# ControlBoardUsb.net
KiCad netlist of a schematic drawn in EAGLE
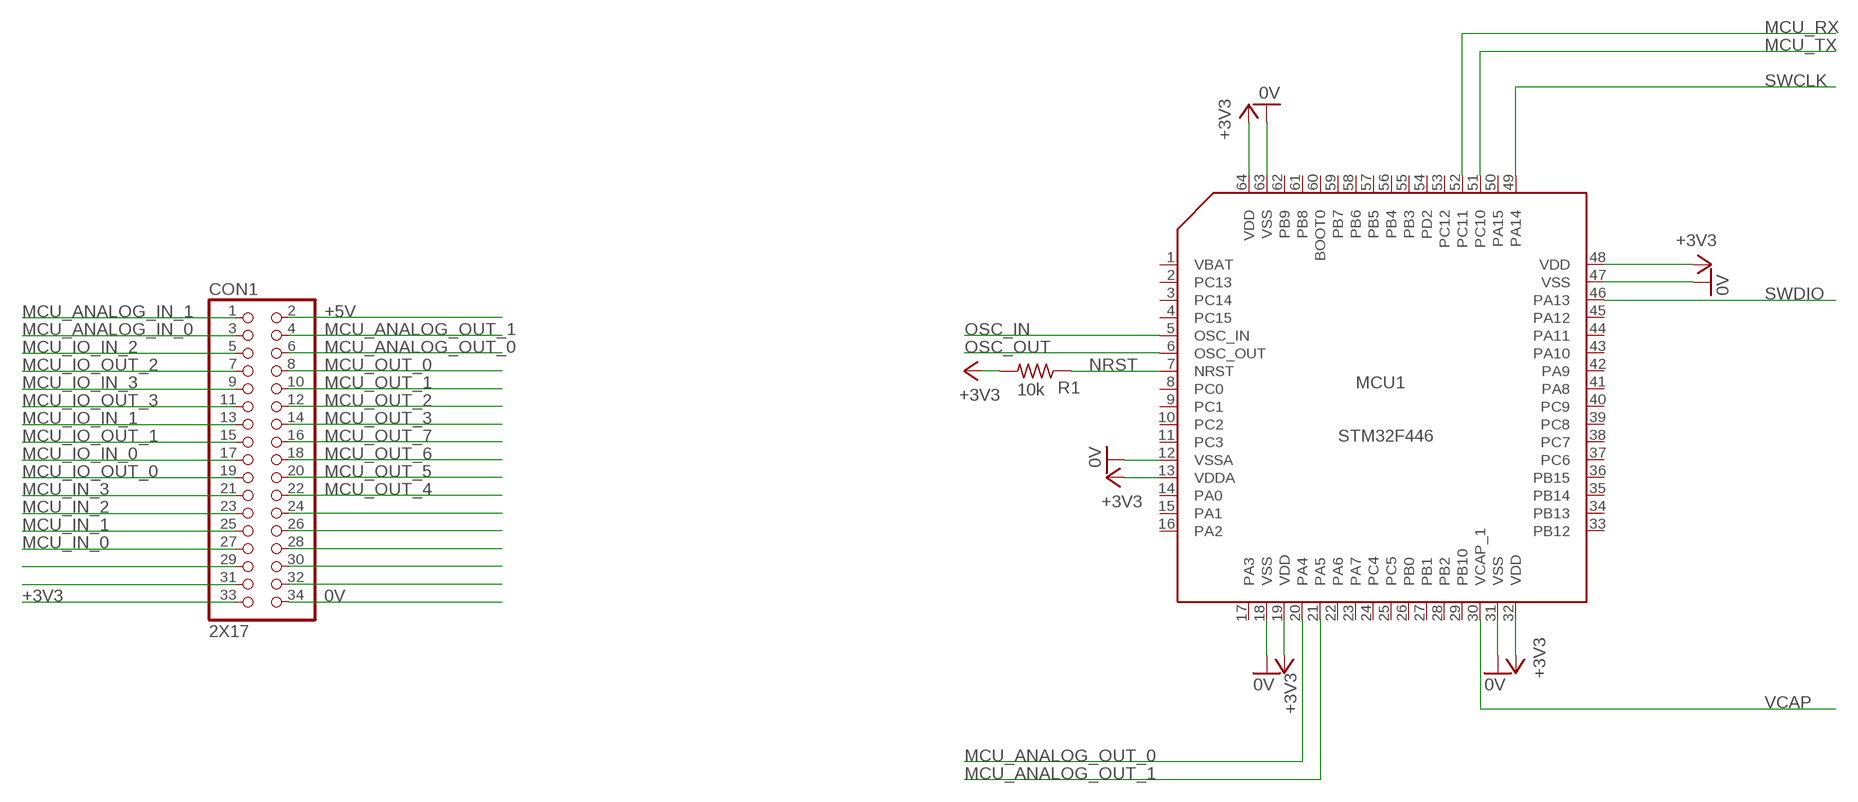
[diagram p0: schematic, sheet 1, part 1 of 2]
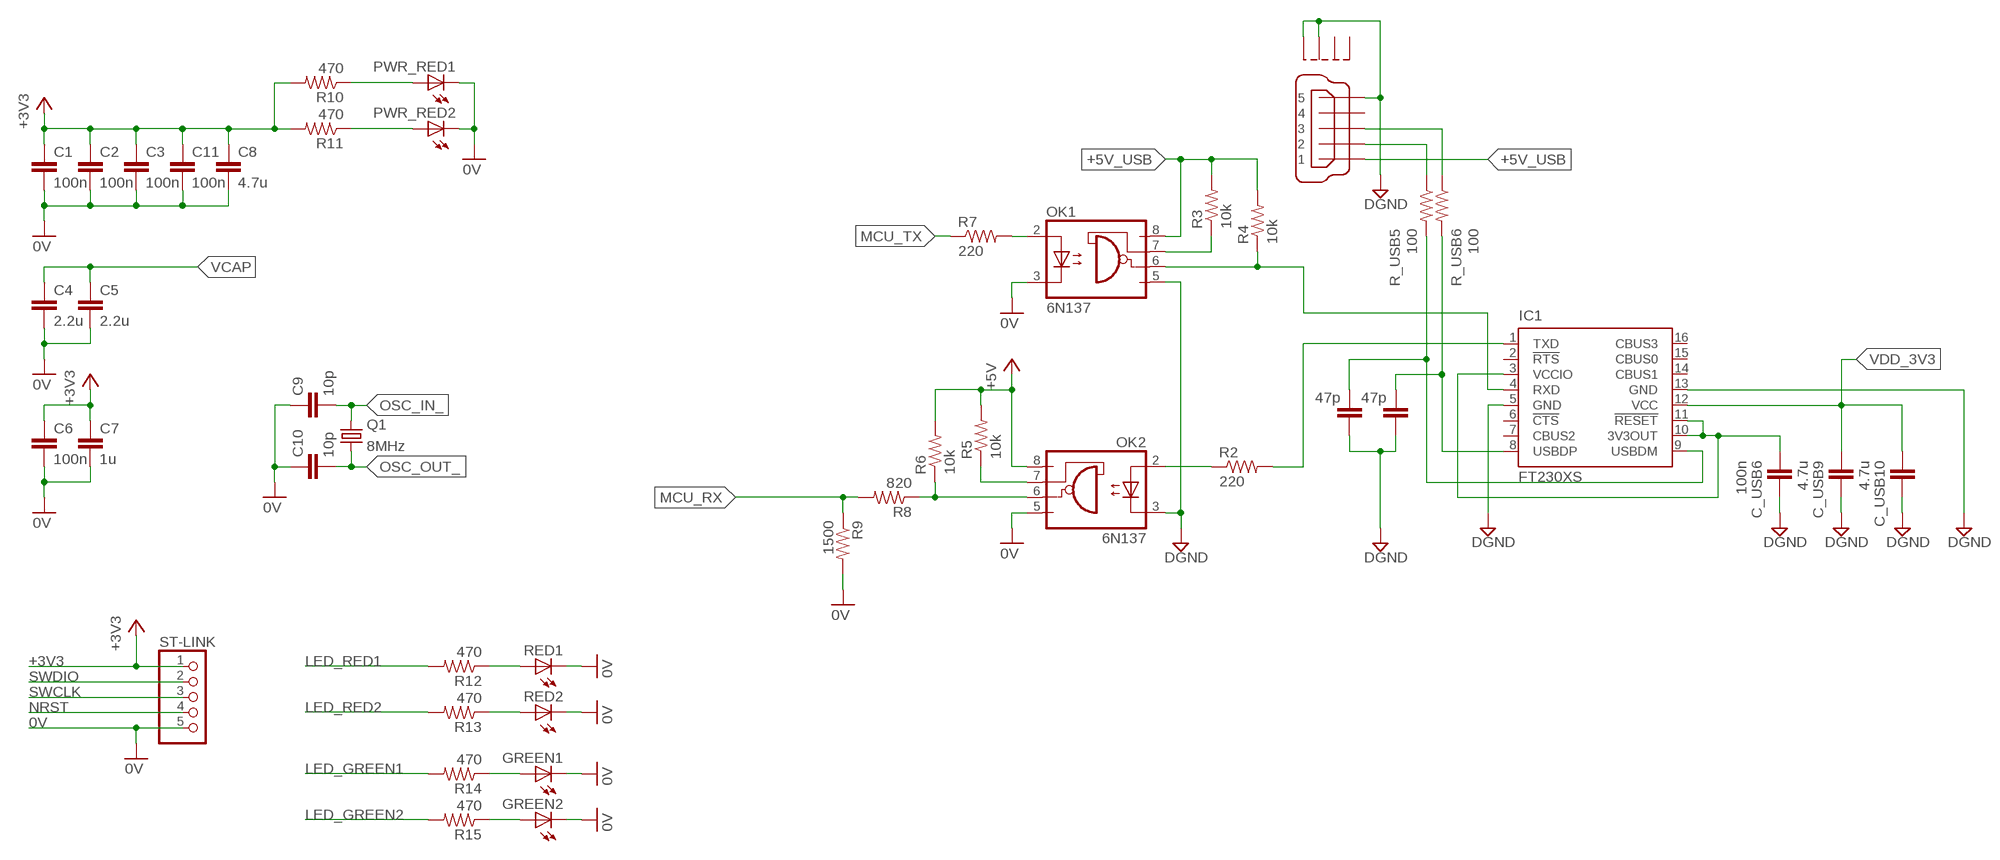
[diagram p1: schematic, sheet 1, part 2 of 2]

(export (version "E")
  (design (tool "Eeschema 10.0.6"))
  (components
    (comp (ref "C1")
      (value "100n")
      (footprint "eagle-import:C0402")
      (libsource (lib "eagle-import") (part "C-EUC0402"))
    )
    (comp (ref "C2")
      (value "100n")
      (footprint "eagle-import:C0402")
      (libsource (lib "eagle-import") (part "C-EUC0402"))
    )
    (comp (ref "C3")
      (value "100n")
      (footprint "eagle-import:C0402")
      (libsource (lib "eagle-import") (part "C-EUC0402"))
    )
    (comp (ref "C4")
      (value "2.2u")
      (footprint "eagle-import:C0402")
      (libsource (lib "eagle-import") (part "C-EUC0402"))
    )
    (comp (ref "C5")
      (value "2.2u")
      (footprint "eagle-import:C0402")
      (libsource (lib "eagle-import") (part "C-EUC0402"))
    )
    (comp (ref "C6")
      (value "100n")
      (footprint "eagle-import:C0402")
      (libsource (lib "eagle-import") (part "C-EUC0402"))
    )
    (comp (ref "C7")
      (value "1u")
      (footprint "eagle-import:C0402")
      (libsource (lib "eagle-import") (part "C-EUC0402"))
    )
    (comp (ref "C8")
      (value "4.7u")
      (footprint "eagle-import:C0402")
      (libsource (lib "eagle-import") (part "C-EUC0402"))
    )
    (comp (ref "C9")
      (value "10p")
      (footprint "eagle-import:C0402")
      (libsource (lib "eagle-import") (part "C-EUC0402"))
    )
    (comp (ref "C10")
      (value "10p")
      (footprint "eagle-import:C0402")
      (libsource (lib "eagle-import") (part "C-EUC0402"))
    )
    (comp (ref "C11")
      (value "100n")
      (footprint "eagle-import:C0402")
      (libsource (lib "eagle-import") (part "C-EUC0402"))
    )
    (comp (ref "CON1")
      (value "2X17")
      (footprint "eagle-import:2X17")
      (libsource (lib "eagle-import") (part "2X17"))
    )
    (comp (ref "CON3")
      (value "MICRO_USB_TYPE_A")
      (footprint "eagle-import:MINI_USB_TYPE_A_THOLE")
      (libsource (lib "eagle-import") (part "MICRO_USB_TYPE_A"))
    )
    (comp (ref "C_USB6")
      (value "100n")
      (footprint "eagle-import:C0402")
      (libsource (lib "eagle-import") (part "C-EUC0402"))
    )
    (comp (ref "C_USB7")
      (value "47p")
      (footprint "eagle-import:C0402")
      (libsource (lib "eagle-import") (part "C-EUC0402"))
    )
    (comp (ref "C_USB8")
      (value "47p")
      (footprint "eagle-import:C0402")
      (libsource (lib "eagle-import") (part "C-EUC0402"))
    )
    (comp (ref "C_USB9")
      (value "4.7u")
      (footprint "eagle-import:C0402")
      (libsource (lib "eagle-import") (part "C-EUC0402"))
    )
    (comp (ref "C_USB10")
      (value "4.7u")
      (footprint "eagle-import:C0402")
      (libsource (lib "eagle-import") (part "C-EUC0402"))
    )
    (comp (ref "GREEN1")
      (value "LEDCHIP-LED0805")
      (footprint "eagle-import:CHIP-LED0805")
      (libsource (lib "eagle-import") (part "LEDCHIP-LED0805"))
    )
    (comp (ref "GREEN2")
      (value "LEDCHIP-LED0805")
      (footprint "eagle-import:CHIP-LED0805")
      (libsource (lib "eagle-import") (part "LEDCHIP-LED0805"))
    )
    (comp (ref "IC1")
      (value "FT230XS")
      (footprint "eagle-import:SSOP16")
      (libsource (lib "eagle-import") (part "FT230XS"))
    )
    (comp (ref "MCU1")
      (value "STM32F446")
      (footprint "eagle-import:LQFP-64")
      (libsource (lib "eagle-import") (part "STM32F446"))
    )
    (comp (ref "OK1")
      (value "6N137")
      (footprint "eagle-import:DIL08")
      (libsource (lib "eagle-import") (part "6N137"))
    )
    (comp (ref "OK2")
      (value "6N137")
      (footprint "eagle-import:DIL08")
      (libsource (lib "eagle-import") (part "6N137"))
    )
    (comp (ref "PWR_RED1")
      (value "LEDCHIP-LED0805")
      (footprint "eagle-import:CHIP-LED0805")
      (libsource (lib "eagle-import") (part "LEDCHIP-LED0805"))
    )
    (comp (ref "PWR_RED2")
      (value "LEDCHIP-LED0805")
      (footprint "eagle-import:CHIP-LED0805")
      (libsource (lib "eagle-import") (part "LEDCHIP-LED0805"))
    )
    (comp (ref "Q1")
      (value "8MHz")
      (footprint "eagle-import:HC33U-V")
      (libsource (lib "eagle-import") (part "CRYSTALHC33U-V"))
    )
    (comp (ref "R1")
      (value "10k")
      (footprint "eagle-import:R0402")
      (libsource (lib "eagle-import") (part "R-US_R0402"))
    )
    (comp (ref "R2")
      (value "220")
      (footprint "eagle-import:R0402")
      (libsource (lib "eagle-import") (part "R-US_R0402"))
    )
    (comp (ref "R3")
      (value "10k")
      (footprint "eagle-import:R0402")
      (libsource (lib "eagle-import") (part "R-US_R0402"))
    )
    (comp (ref "R4")
      (value "10k")
      (footprint "eagle-import:R0402")
      (libsource (lib "eagle-import") (part "R-US_R0402"))
    )
    (comp (ref "R5")
      (value "10k")
      (footprint "eagle-import:R0402")
      (libsource (lib "eagle-import") (part "R-US_R0402"))
    )
    (comp (ref "R6")
      (value "10k")
      (footprint "eagle-import:R0402")
      (libsource (lib "eagle-import") (part "R-US_R0402"))
    )
    (comp (ref "R7")
      (value "220")
      (footprint "eagle-import:R0402")
      (libsource (lib "eagle-import") (part "R-US_R0402"))
    )
    (comp (ref "R8")
      (value "820")
      (footprint "eagle-import:R0402")
      (libsource (lib "eagle-import") (part "R-US_R0402"))
    )
    (comp (ref "R9")
      (value "1500")
      (footprint "eagle-import:R0402")
      (libsource (lib "eagle-import") (part "R-US_R0402"))
    )
    (comp (ref "R10")
      (value "470")
      (footprint "eagle-import:R0402")
      (libsource (lib "eagle-import") (part "R-US_R0402"))
    )
    (comp (ref "R11")
      (value "470")
      (footprint "eagle-import:R0402")
      (libsource (lib "eagle-import") (part "R-US_R0402"))
    )
    (comp (ref "R12")
      (value "470")
      (footprint "eagle-import:R0402")
      (libsource (lib "eagle-import") (part "R-US_R0402"))
    )
    (comp (ref "R13")
      (value "470")
      (footprint "eagle-import:R0402")
      (libsource (lib "eagle-import") (part "R-US_R0402"))
    )
    (comp (ref "R14")
      (value "470")
      (footprint "eagle-import:R0402")
      (libsource (lib "eagle-import") (part "R-US_R0402"))
    )
    (comp (ref "R15")
      (value "470")
      (footprint "eagle-import:R0402")
      (libsource (lib "eagle-import") (part "R-US_R0402"))
    )
    (comp (ref "RED1")
      (value "LEDCHIP-LED0805")
      (footprint "eagle-import:CHIP-LED0805")
      (libsource (lib "eagle-import") (part "LEDCHIP-LED0805"))
    )
    (comp (ref "RED2")
      (value "LEDCHIP-LED0805")
      (footprint "eagle-import:CHIP-LED0805")
      (libsource (lib "eagle-import") (part "LEDCHIP-LED0805"))
    )
    (comp (ref "R_USB5")
      (value "100")
      (footprint "eagle-import:R0402")
      (libsource (lib "eagle-import") (part "R-US_R0402"))
    )
    (comp (ref "R_USB6")
      (value "100")
      (footprint "eagle-import:R0402")
      (libsource (lib "eagle-import") (part "R-US_R0402"))
    )
    (comp (ref "ST-LINK")
      (value "PINHD-1X5/90")
      (footprint "eagle-import:1X05_90")
      (libsource (lib "eagle-import") (part "PINHD-1X5/90"))
    )
  )
  (nets
    (net (code "1") (name "+3V3") (class "Default")
      (node (ref "C1") (pin "1") (pinfunction "1_1") (pintype "passive"))
      (node (ref "C11") (pin "1") (pinfunction "1_1") (pintype "passive"))
      (node (ref "C2") (pin "1") (pinfunction "1_1") (pintype "passive"))
      (node (ref "C3") (pin "1") (pinfunction "1_1") (pintype "passive"))
      (node (ref "C6") (pin "1") (pinfunction "1_1") (pintype "passive"))
      (node (ref "C7") (pin "1") (pinfunction "1_1") (pintype "passive"))
      (node (ref "C8") (pin "1") (pinfunction "1_1") (pintype "passive"))
      (node (ref "CON1") (pin "33") (pinfunction "33_33") (pintype "passive"))
      (node (ref "MCU1") (pin "13") (pinfunction "VDDA_13") (pintype "bidirectional"))
      (node (ref "MCU1") (pin "19") (pinfunction "VDD_19") (pintype "bidirectional"))
      (node (ref "MCU1") (pin "32") (pinfunction "VDD_32") (pintype "bidirectional"))
      (node (ref "MCU1") (pin "48") (pinfunction "VDD_48") (pintype "bidirectional"))
      (node (ref "MCU1") (pin "64") (pinfunction "VDD_64") (pintype "bidirectional"))
      (node (ref "R1") (pin "2") (pinfunction "2_2") (pintype "passive"))
      (node (ref "R10") (pin "2") (pinfunction "2_2") (pintype "passive"))
      (node (ref "R11") (pin "2") (pinfunction "2_2") (pintype "passive"))
      (node (ref "ST-LINK") (pin "1") (pinfunction "1_1") (pintype "passive"))
    )
    (net (code "2") (name "+5V") (class "Default")
      (node (ref "CON1") (pin "2") (pinfunction "2_2") (pintype "passive"))
      (node (ref "OK2") (pin "8") (pinfunction "VCC_8") (pintype "passive"))
      (node (ref "R5") (pin "2") (pinfunction "2_2") (pintype "passive"))
      (node (ref "R6") (pin "2") (pinfunction "2_2") (pintype "passive"))
    )
    (net (code "3") (name "+5V_USB") (class "Default")
      (node (ref "CON3") (pin "1") (pinfunction "1_1") (pintype "passive"))
      (node (ref "OK1") (pin "8") (pinfunction "VCC_8") (pintype "passive"))
      (node (ref "R3") (pin "2") (pinfunction "2_2") (pintype "passive"))
      (node (ref "R4") (pin "2") (pinfunction "2_2") (pintype "passive"))
    )
    (net (code "4") (name "/LED_GREEN1") (class "Default")
      (node (ref "R14") (pin "2") (pinfunction "2_2") (pintype "passive"))
    )
    (net (code "5") (name "/LED_GREEN2") (class "Default")
      (node (ref "R15") (pin "2") (pinfunction "2_2") (pintype "passive"))
    )
    (net (code "6") (name "/LED_RED1") (class "Default")
      (node (ref "R12") (pin "2") (pinfunction "2_2") (pintype "passive"))
    )
    (net (code "7") (name "/LED_RED2") (class "Default")
      (node (ref "R13") (pin "2") (pinfunction "2_2") (pintype "passive"))
    )
    (net (code "8") (name "/MCU_ANALOG_IN_0") (class "Default")
      (node (ref "CON1") (pin "3") (pinfunction "3_3") (pintype "passive"))
    )
    (net (code "9") (name "/MCU_ANALOG_IN_1") (class "Default")
      (node (ref "CON1") (pin "1") (pinfunction "1_1") (pintype "passive"))
    )
    (net (code "10") (name "/MCU_ANALOG_OUT_0") (class "Default")
      (node (ref "CON1") (pin "6") (pinfunction "6_6") (pintype "passive"))
      (node (ref "MCU1") (pin "20") (pinfunction "PA4_20") (pintype "bidirectional"))
    )
    (net (code "11") (name "/MCU_ANALOG_OUT_1") (class "Default")
      (node (ref "CON1") (pin "4") (pinfunction "4_4") (pintype "passive"))
      (node (ref "MCU1") (pin "21") (pinfunction "PA5_21") (pintype "bidirectional"))
    )
    (net (code "12") (name "/MCU_IN_0") (class "Default")
      (node (ref "CON1") (pin "27") (pinfunction "27_27") (pintype "passive"))
    )
    (net (code "13") (name "/MCU_IN_1") (class "Default")
      (node (ref "CON1") (pin "25") (pinfunction "25_25") (pintype "passive"))
    )
    (net (code "14") (name "/MCU_IN_2") (class "Default")
      (node (ref "CON1") (pin "23") (pinfunction "23_23") (pintype "passive"))
    )
    (net (code "15") (name "/MCU_IN_3") (class "Default")
      (node (ref "CON1") (pin "21") (pinfunction "21_21") (pintype "passive"))
    )
    (net (code "16") (name "/MCU_IO_IN_0") (class "Default")
      (node (ref "CON1") (pin "17") (pinfunction "17_17") (pintype "passive"))
    )
    (net (code "17") (name "/MCU_IO_IN_1") (class "Default")
      (node (ref "CON1") (pin "13") (pinfunction "13_13") (pintype "passive"))
    )
    (net (code "18") (name "/MCU_IO_IN_2") (class "Default")
      (node (ref "CON1") (pin "5") (pinfunction "5_5") (pintype "passive"))
    )
    (net (code "19") (name "/MCU_IO_IN_3") (class "Default")
      (node (ref "CON1") (pin "9") (pinfunction "9_9") (pintype "passive"))
    )
    (net (code "20") (name "/MCU_IO_OUT_0") (class "Default")
      (node (ref "CON1") (pin "19") (pinfunction "19_19") (pintype "passive"))
    )
    (net (code "21") (name "/MCU_IO_OUT_1") (class "Default")
      (node (ref "CON1") (pin "15") (pinfunction "15_15") (pintype "passive"))
    )
    (net (code "22") (name "/MCU_IO_OUT_2") (class "Default")
      (node (ref "CON1") (pin "7") (pinfunction "7_7") (pintype "passive"))
    )
    (net (code "23") (name "/MCU_IO_OUT_3") (class "Default")
      (node (ref "CON1") (pin "11") (pinfunction "11_11") (pintype "passive"))
    )
    (net (code "24") (name "/MCU_OUT_0") (class "Default")
      (node (ref "CON1") (pin "8") (pinfunction "8_8") (pintype "passive"))
    )
    (net (code "25") (name "/MCU_OUT_1") (class "Default")
      (node (ref "CON1") (pin "10") (pinfunction "10_10") (pintype "passive"))
    )
    (net (code "26") (name "/MCU_OUT_2") (class "Default")
      (node (ref "CON1") (pin "12") (pinfunction "12_12") (pintype "passive"))
    )
    (net (code "27") (name "/MCU_OUT_3") (class "Default")
      (node (ref "CON1") (pin "14") (pinfunction "14_14") (pintype "passive"))
    )
    (net (code "28") (name "/MCU_OUT_4") (class "Default")
      (node (ref "CON1") (pin "22") (pinfunction "22_22") (pintype "passive"))
    )
    (net (code "29") (name "/MCU_OUT_5") (class "Default")
      (node (ref "CON1") (pin "20") (pinfunction "20_20") (pintype "passive"))
    )
    (net (code "30") (name "/MCU_OUT_6") (class "Default")
      (node (ref "CON1") (pin "18") (pinfunction "18_18") (pintype "passive"))
    )
    (net (code "31") (name "/MCU_OUT_7") (class "Default")
      (node (ref "CON1") (pin "16") (pinfunction "16_16") (pintype "passive"))
    )
    (net (code "32") (name "/NRST") (class "Default")
      (node (ref "MCU1") (pin "7") (pinfunction "NRST_7") (pintype "bidirectional"))
      (node (ref "R1") (pin "1") (pinfunction "1_1") (pintype "passive"))
      (node (ref "ST-LINK") (pin "4") (pinfunction "4_4") (pintype "passive"))
    )
    (net (code "33") (name "/OSC_IN") (class "Default")
      (node (ref "MCU1") (pin "5") (pinfunction "OSC_IN_5") (pintype "bidirectional"))
    )
    (net (code "34") (name "/OSC_OUT") (class "Default")
      (node (ref "MCU1") (pin "6") (pinfunction "OSC_OUT_6") (pintype "bidirectional"))
    )
    (net (code "35") (name "/SWCLK") (class "Default")
      (node (ref "MCU1") (pin "49") (pinfunction "PA14_49") (pintype "bidirectional"))
      (node (ref "ST-LINK") (pin "3") (pinfunction "3_3") (pintype "passive"))
    )
    (net (code "36") (name "/SWDIO") (class "Default")
      (node (ref "MCU1") (pin "46") (pinfunction "PA13_46") (pintype "bidirectional"))
      (node (ref "ST-LINK") (pin "2") (pinfunction "2_2") (pintype "passive"))
    )
    (net (code "37") (name "0V") (class "Default")
      (node (ref "C1") (pin "2") (pinfunction "2_2") (pintype "passive"))
      (node (ref "C10") (pin "1") (pinfunction "1_1") (pintype "passive"))
      (node (ref "C11") (pin "2") (pinfunction "2_2") (pintype "passive"))
      (node (ref "C2") (pin "2") (pinfunction "2_2") (pintype "passive"))
      (node (ref "C3") (pin "2") (pinfunction "2_2") (pintype "passive"))
      (node (ref "C4") (pin "2") (pinfunction "2_2") (pintype "passive"))
      (node (ref "C5") (pin "2") (pinfunction "2_2") (pintype "passive"))
      (node (ref "C6") (pin "2") (pinfunction "2_2") (pintype "passive"))
      (node (ref "C7") (pin "2") (pinfunction "2_2") (pintype "passive"))
      (node (ref "C8") (pin "2") (pinfunction "2_2") (pintype "passive"))
      (node (ref "C9") (pin "1") (pinfunction "1_1") (pintype "passive"))
      (node (ref "CON1") (pin "34") (pinfunction "34_34") (pintype "passive"))
      (node (ref "GREEN1") (pin "C") (pinfunction "C_C") (pintype "passive"))
      (node (ref "GREEN2") (pin "C") (pinfunction "C_C") (pintype "passive"))
      (node (ref "MCU1") (pin "12") (pinfunction "VSSA_12") (pintype "bidirectional"))
      (node (ref "MCU1") (pin "18") (pinfunction "VSS_18") (pintype "bidirectional"))
      (node (ref "MCU1") (pin "31") (pinfunction "VSS_31") (pintype "bidirectional"))
      (node (ref "MCU1") (pin "47") (pinfunction "VSS_47") (pintype "bidirectional"))
      (node (ref "MCU1") (pin "63") (pinfunction "VSS_63") (pintype "bidirectional"))
      (node (ref "OK1") (pin "3") (pinfunction "C_3") (pintype "passive"))
      (node (ref "OK2") (pin "5") (pinfunction "GND_5") (pintype "passive"))
      (node (ref "PWR_RED1") (pin "C") (pinfunction "C_C") (pintype "passive"))
      (node (ref "PWR_RED2") (pin "C") (pinfunction "C_C") (pintype "passive"))
      (node (ref "R9") (pin "2") (pinfunction "2_2") (pintype "passive"))
      (node (ref "RED1") (pin "C") (pinfunction "C_C") (pintype "passive"))
      (node (ref "RED2") (pin "C") (pinfunction "C_C") (pintype "passive"))
      (node (ref "ST-LINK") (pin "5") (pinfunction "5_5") (pintype "passive"))
    )
    (net (code "38") (name "DGND") (class "Default")
      (node (ref "CON3") (pin "5") (pinfunction "5_5") (pintype "passive"))
      (node (ref "CON3") (pin "M3") (pinfunction "S3_M3") (pintype "passive"))
      (node (ref "CON3") (pin "M4") (pinfunction "S4_M4") (pintype "passive"))
      (node (ref "C_USB10") (pin "1") (pinfunction "1_1") (pintype "passive"))
      (node (ref "C_USB6") (pin "1") (pinfunction "1_1") (pintype "passive"))
      (node (ref "C_USB7") (pin "1") (pinfunction "1_1") (pintype "passive"))
      (node (ref "C_USB8") (pin "1") (pinfunction "1_1") (pintype "passive"))
      (node (ref "C_USB9") (pin "1") (pinfunction "1_1") (pintype "passive"))
      (node (ref "IC1") (pin "13") (pinfunction "GND_13") (pintype "power_in"))
      (node (ref "IC1") (pin "5") (pinfunction "GND_5") (pintype "power_in"))
      (node (ref "OK1") (pin "5") (pinfunction "GND_5") (pintype "passive"))
      (node (ref "OK2") (pin "3") (pinfunction "C_3") (pintype "passive"))
    )
    (net (code "39") (name "MCU_RX") (class "Default")
      (node (ref "MCU1") (pin "52") (pinfunction "PC11_52") (pintype "bidirectional"))
      (node (ref "R8") (pin "2") (pinfunction "2_2") (pintype "passive"))
      (node (ref "R9") (pin "1") (pinfunction "1_1") (pintype "passive"))
    )
    (net (code "40") (name "MCU_TX") (class "Default")
      (node (ref "MCU1") (pin "51") (pinfunction "PC10_51") (pintype "bidirectional"))
      (node (ref "R7") (pin "1") (pinfunction "1_1") (pintype "passive"))
    )
    (net (code "41") (name "Net-(CON3-Pad2)") (class "Default")
      (node (ref "CON3") (pin "2") (pinfunction "2_2") (pintype "passive"))
      (node (ref "R_USB5") (pin "1") (pinfunction "1_1") (pintype "passive"))
    )
    (net (code "42") (name "Net-(CON3-Pad3)") (class "Default")
      (node (ref "CON3") (pin "3") (pinfunction "3_3") (pintype "passive"))
      (node (ref "R_USB6") (pin "1") (pinfunction "1_1") (pintype "passive"))
    )
    (net (code "43") (name "Net-(GREEN1-PadA)") (class "Default")
      (node (ref "GREEN1") (pin "A") (pinfunction "A_A") (pintype "passive"))
      (node (ref "R14") (pin "1") (pinfunction "1_1") (pintype "passive"))
    )
    (net (code "44") (name "Net-(GREEN2-PadA)") (class "Default")
      (node (ref "GREEN2") (pin "A") (pinfunction "A_A") (pintype "passive"))
      (node (ref "R15") (pin "1") (pinfunction "1_1") (pintype "passive"))
    )
    (net (code "45") (name "Net-(IC1-3V3OUT)") (class "Default")
      (node (ref "C_USB6") (pin "2") (pinfunction "2_2") (pintype "passive"))
      (node (ref "IC1") (pin "10") (pinfunction "3V3OUT_10") (pintype "output"))
      (node (ref "IC1") (pin "11") (pinfunction "~{RESET}_11") (pintype "input"))
      (node (ref "IC1") (pin "3") (pinfunction "VCCIO_3") (pintype "power_in"))
    )
    (net (code "46") (name "Net-(IC1-RXD)") (class "Default")
      (node (ref "IC1") (pin "4") (pinfunction "RXD_4") (pintype "input"))
      (node (ref "OK1") (pin "6") (pinfunction "VO_6") (pintype "passive"))
      (node (ref "R4") (pin "1") (pinfunction "1_1") (pintype "passive"))
    )
    (net (code "47") (name "Net-(IC1-TXD)") (class "Default")
      (node (ref "IC1") (pin "1") (pinfunction "TXD_1") (pintype "output"))
      (node (ref "R2") (pin "2") (pinfunction "2_2") (pintype "passive"))
    )
    (net (code "48") (name "Net-(IC1-USBDM)") (class "Default")
      (node (ref "C_USB7") (pin "2") (pinfunction "2_2") (pintype "passive"))
      (node (ref "IC1") (pin "9") (pinfunction "USBDM_9") (pintype "input"))
      (node (ref "R_USB5") (pin "2") (pinfunction "2_2") (pintype "passive"))
    )
    (net (code "49") (name "Net-(IC1-USBDP)") (class "Default")
      (node (ref "C_USB8") (pin "2") (pinfunction "2_2") (pintype "passive"))
      (node (ref "IC1") (pin "8") (pinfunction "USBDP_8") (pintype "input"))
      (node (ref "R_USB6") (pin "2") (pinfunction "2_2") (pintype "passive"))
    )
    (net (code "50") (name "Net-(OK1-A)") (class "Default")
      (node (ref "OK1") (pin "2") (pinfunction "A_2") (pintype "passive"))
      (node (ref "R7") (pin "2") (pinfunction "2_2") (pintype "passive"))
    )
    (net (code "51") (name "Net-(OK1-VE)") (class "Default")
      (node (ref "OK1") (pin "7") (pinfunction "VE_7") (pintype "passive"))
      (node (ref "R3") (pin "1") (pinfunction "1_1") (pintype "passive"))
    )
    (net (code "52") (name "Net-(OK2-A)") (class "Default")
      (node (ref "OK2") (pin "2") (pinfunction "A_2") (pintype "passive"))
      (node (ref "R2") (pin "1") (pinfunction "1_1") (pintype "passive"))
    )
    (net (code "53") (name "Net-(OK2-VE)") (class "Default")
      (node (ref "OK2") (pin "7") (pinfunction "VE_7") (pintype "passive"))
      (node (ref "R5") (pin "1") (pinfunction "1_1") (pintype "passive"))
    )
    (net (code "54") (name "Net-(OK2-VO)") (class "Default")
      (node (ref "OK2") (pin "6") (pinfunction "VO_6") (pintype "passive"))
      (node (ref "R6") (pin "1") (pinfunction "1_1") (pintype "passive"))
      (node (ref "R8") (pin "1") (pinfunction "1_1") (pintype "passive"))
    )
    (net (code "55") (name "Net-(PWR_RED1-PadA)") (class "Default")
      (node (ref "PWR_RED1") (pin "A") (pinfunction "A_A") (pintype "passive"))
      (node (ref "R10") (pin "1") (pinfunction "1_1") (pintype "passive"))
    )
    (net (code "56") (name "Net-(PWR_RED2-PadA)") (class "Default")
      (node (ref "PWR_RED2") (pin "A") (pinfunction "A_A") (pintype "passive"))
      (node (ref "R11") (pin "1") (pinfunction "1_1") (pintype "passive"))
    )
    (net (code "57") (name "Net-(R12-Pad1)") (class "Default")
      (node (ref "R12") (pin "1") (pinfunction "1_1") (pintype "passive"))
      (node (ref "RED1") (pin "A") (pinfunction "A_A") (pintype "passive"))
    )
    (net (code "58") (name "Net-(R13-Pad1)") (class "Default")
      (node (ref "R13") (pin "1") (pinfunction "1_1") (pintype "passive"))
      (node (ref "RED2") (pin "A") (pinfunction "A_A") (pintype "passive"))
    )
    (net (code "59") (name "OSC_IN_") (class "Default")
      (node (ref "C9") (pin "2") (pinfunction "2_2") (pintype "passive"))
      (node (ref "Q1") (pin "2") (pinfunction "2_2") (pintype "passive"))
    )
    (net (code "60") (name "OSC_OUT_") (class "Default")
      (node (ref "C10") (pin "2") (pinfunction "2_2") (pintype "passive"))
      (node (ref "Q1") (pin "1") (pinfunction "1_1") (pintype "passive"))
    )
    (net (code "61") (name "VCAP") (class "Default")
      (node (ref "C4") (pin "1") (pinfunction "1_1") (pintype "passive"))
      (node (ref "C5") (pin "1") (pinfunction "1_1") (pintype "passive"))
      (node (ref "MCU1") (pin "30") (pinfunction "VCAP_1_30") (pintype "bidirectional"))
    )
    (net (code "62") (name "VDD_3V3") (class "Default")
      (node (ref "C_USB10") (pin "2") (pinfunction "2_2") (pintype "passive"))
      (node (ref "C_USB9") (pin "2") (pinfunction "2_2") (pintype "passive"))
      (node (ref "IC1") (pin "12") (pinfunction "VCC_12") (pintype "power_in"))
    )
    (net (code "63") (name "unconnected-(CON1-Pad24)") (class "Default")
      (node (ref "CON1") (pin "24") (pinfunction "24_24") (pintype "passive"))
    )
    (net (code "64") (name "unconnected-(CON1-Pad26)") (class "Default")
      (node (ref "CON1") (pin "26") (pinfunction "26_26") (pintype "passive"))
    )
    (net (code "65") (name "unconnected-(CON1-Pad28)") (class "Default")
      (node (ref "CON1") (pin "28") (pinfunction "28_28") (pintype "passive"))
    )
    (net (code "66") (name "unconnected-(CON1-Pad29)") (class "Default")
      (node (ref "CON1") (pin "29") (pinfunction "29_29") (pintype "passive"))
    )
    (net (code "67") (name "unconnected-(CON1-Pad30)") (class "Default")
      (node (ref "CON1") (pin "30") (pinfunction "30_30") (pintype "passive"))
    )
    (net (code "68") (name "unconnected-(CON1-Pad31)") (class "Default")
      (node (ref "CON1") (pin "31") (pinfunction "31_31") (pintype "passive"))
    )
    (net (code "69") (name "unconnected-(CON1-Pad32)") (class "Default")
      (node (ref "CON1") (pin "32") (pinfunction "32_32") (pintype "passive"))
    )
    (net (code "70") (name "unconnected-(CON3-Pad4)") (class "Default")
      (node (ref "CON3") (pin "4") (pinfunction "4_4") (pintype "passive"))
    )
    (net (code "71") (name "unconnected-(CON3B-S1-PadM1)") (class "Default")
      (node (ref "CON3") (pin "M1") (pinfunction "S1_M1") (pintype "passive"))
    )
    (net (code "72") (name "unconnected-(CON3B-S2-PadM2)") (class "Default")
      (node (ref "CON3") (pin "M2") (pinfunction "S2_M2") (pintype "passive"))
    )
    (net (code "73") (name "unconnected-(IC1-CBUS0-Pad15)") (class "Default")
      (node (ref "IC1") (pin "15") (pinfunction "CBUS0_15") (pintype "bidirectional"))
    )
    (net (code "74") (name "unconnected-(IC1-CBUS1-Pad14)") (class "Default")
      (node (ref "IC1") (pin "14") (pinfunction "CBUS1_14") (pintype "bidirectional"))
    )
    (net (code "75") (name "unconnected-(IC1-CBUS2-Pad7)") (class "Default")
      (node (ref "IC1") (pin "7") (pinfunction "CBUS2_7") (pintype "bidirectional"))
    )
    (net (code "76") (name "unconnected-(IC1-CBUS3-Pad16)") (class "Default")
      (node (ref "IC1") (pin "16") (pinfunction "CBUS3_16") (pintype "bidirectional"))
    )
    (net (code "77") (name "unconnected-(IC1-~{CTS}-Pad6)") (class "Default")
      (node (ref "IC1") (pin "6") (pinfunction "~{CTS}_6") (pintype "input"))
    )
    (net (code "78") (name "unconnected-(IC1-~{RTS}-Pad2)") (class "Default")
      (node (ref "IC1") (pin "2") (pinfunction "~{RTS}_2") (pintype "output"))
    )
    (net (code "79") (name "unconnected-(MCU1-BOOT0-Pad60)") (class "Default")
      (node (ref "MCU1") (pin "60") (pinfunction "BOOT0_60") (pintype "bidirectional"))
    )
    (net (code "80") (name "unconnected-(MCU1-PA0-Pad14)") (class "Default")
      (node (ref "MCU1") (pin "14") (pinfunction "PA0_14") (pintype "bidirectional"))
    )
    (net (code "81") (name "unconnected-(MCU1-PA1-Pad15)") (class "Default")
      (node (ref "MCU1") (pin "15") (pinfunction "PA1_15") (pintype "bidirectional"))
    )
    (net (code "82") (name "unconnected-(MCU1-PA2-Pad16)") (class "Default")
      (node (ref "MCU1") (pin "16") (pinfunction "PA2_16") (pintype "bidirectional"))
    )
    (net (code "83") (name "unconnected-(MCU1-PA3-Pad17)") (class "Default")
      (node (ref "MCU1") (pin "17") (pinfunction "PA3_17") (pintype "bidirectional"))
    )
    (net (code "84") (name "unconnected-(MCU1-PA6-Pad22)") (class "Default")
      (node (ref "MCU1") (pin "22") (pinfunction "PA6_22") (pintype "bidirectional"))
    )
    (net (code "85") (name "unconnected-(MCU1-PA7-Pad23)") (class "Default")
      (node (ref "MCU1") (pin "23") (pinfunction "PA7_23") (pintype "bidirectional"))
    )
    (net (code "86") (name "unconnected-(MCU1-PA8-Pad41)") (class "Default")
      (node (ref "MCU1") (pin "41") (pinfunction "PA8_41") (pintype "bidirectional"))
    )
    (net (code "87") (name "unconnected-(MCU1-PA9-Pad42)") (class "Default")
      (node (ref "MCU1") (pin "42") (pinfunction "PA9_42") (pintype "bidirectional"))
    )
    (net (code "88") (name "unconnected-(MCU1-PA10-Pad43)") (class "Default")
      (node (ref "MCU1") (pin "43") (pinfunction "PA10_43") (pintype "bidirectional"))
    )
    (net (code "89") (name "unconnected-(MCU1-PA11-Pad44)") (class "Default")
      (node (ref "MCU1") (pin "44") (pinfunction "PA11_44") (pintype "bidirectional"))
    )
    (net (code "90") (name "unconnected-(MCU1-PA12-Pad45)") (class "Default")
      (node (ref "MCU1") (pin "45") (pinfunction "PA12_45") (pintype "bidirectional"))
    )
    (net (code "91") (name "unconnected-(MCU1-PA15-Pad50)") (class "Default")
      (node (ref "MCU1") (pin "50") (pinfunction "PA15_50") (pintype "bidirectional"))
    )
    (net (code "92") (name "unconnected-(MCU1-PB0-Pad26)") (class "Default")
      (node (ref "MCU1") (pin "26") (pinfunction "PB0_26") (pintype "bidirectional"))
    )
    (net (code "93") (name "unconnected-(MCU1-PB1-Pad27)") (class "Default")
      (node (ref "MCU1") (pin "27") (pinfunction "PB1_27") (pintype "bidirectional"))
    )
    (net (code "94") (name "unconnected-(MCU1-PB2-Pad28)") (class "Default")
      (node (ref "MCU1") (pin "28") (pinfunction "PB2_28") (pintype "bidirectional"))
    )
    (net (code "95") (name "unconnected-(MCU1-PB3-Pad55)") (class "Default")
      (node (ref "MCU1") (pin "55") (pinfunction "PB3_55") (pintype "bidirectional"))
    )
    (net (code "96") (name "unconnected-(MCU1-PB4-Pad56)") (class "Default")
      (node (ref "MCU1") (pin "56") (pinfunction "PB4_56") (pintype "bidirectional"))
    )
    (net (code "97") (name "unconnected-(MCU1-PB5-Pad57)") (class "Default")
      (node (ref "MCU1") (pin "57") (pinfunction "PB5_57") (pintype "bidirectional"))
    )
    (net (code "98") (name "unconnected-(MCU1-PB6-Pad58)") (class "Default")
      (node (ref "MCU1") (pin "58") (pinfunction "PB6_58") (pintype "bidirectional"))
    )
    (net (code "99") (name "unconnected-(MCU1-PB7-Pad59)") (class "Default")
      (node (ref "MCU1") (pin "59") (pinfunction "PB7_59") (pintype "bidirectional"))
    )
    (net (code "100") (name "unconnected-(MCU1-PB8-Pad61)") (class "Default")
      (node (ref "MCU1") (pin "61") (pinfunction "PB8_61") (pintype "bidirectional"))
    )
    (net (code "101") (name "unconnected-(MCU1-PB9-Pad62)") (class "Default")
      (node (ref "MCU1") (pin "62") (pinfunction "PB9_62") (pintype "bidirectional"))
    )
    (net (code "102") (name "unconnected-(MCU1-PB10-Pad29)") (class "Default")
      (node (ref "MCU1") (pin "29") (pinfunction "PB10_29") (pintype "bidirectional"))
    )
    (net (code "103") (name "unconnected-(MCU1-PB12-Pad33)") (class "Default")
      (node (ref "MCU1") (pin "33") (pinfunction "PB12_33") (pintype "bidirectional"))
    )
    (net (code "104") (name "unconnected-(MCU1-PB13-Pad34)") (class "Default")
      (node (ref "MCU1") (pin "34") (pinfunction "PB13_34") (pintype "bidirectional"))
    )
    (net (code "105") (name "unconnected-(MCU1-PB14-Pad35)") (class "Default")
      (node (ref "MCU1") (pin "35") (pinfunction "PB14_35") (pintype "bidirectional"))
    )
    (net (code "106") (name "unconnected-(MCU1-PB15-Pad36)") (class "Default")
      (node (ref "MCU1") (pin "36") (pinfunction "PB15_36") (pintype "bidirectional"))
    )
    (net (code "107") (name "unconnected-(MCU1-PC0-Pad8)") (class "Default")
      (node (ref "MCU1") (pin "8") (pinfunction "PC0_8") (pintype "bidirectional"))
    )
    (net (code "108") (name "unconnected-(MCU1-PC1-Pad9)") (class "Default")
      (node (ref "MCU1") (pin "9") (pinfunction "PC1_9") (pintype "bidirectional"))
    )
    (net (code "109") (name "unconnected-(MCU1-PC2-Pad10)") (class "Default")
      (node (ref "MCU1") (pin "10") (pinfunction "PC2_10") (pintype "bidirectional"))
    )
    (net (code "110") (name "unconnected-(MCU1-PC3-Pad11)") (class "Default")
      (node (ref "MCU1") (pin "11") (pinfunction "PC3_11") (pintype "bidirectional"))
    )
    (net (code "111") (name "unconnected-(MCU1-PC4-Pad24)") (class "Default")
      (node (ref "MCU1") (pin "24") (pinfunction "PC4_24") (pintype "bidirectional"))
    )
    (net (code "112") (name "unconnected-(MCU1-PC5-Pad25)") (class "Default")
      (node (ref "MCU1") (pin "25") (pinfunction "PC5_25") (pintype "bidirectional"))
    )
    (net (code "113") (name "unconnected-(MCU1-PC6-Pad37)") (class "Default")
      (node (ref "MCU1") (pin "37") (pinfunction "PC6_37") (pintype "bidirectional"))
    )
    (net (code "114") (name "unconnected-(MCU1-PC7-Pad38)") (class "Default")
      (node (ref "MCU1") (pin "38") (pinfunction "PC7_38") (pintype "bidirectional"))
    )
    (net (code "115") (name "unconnected-(MCU1-PC8-Pad39)") (class "Default")
      (node (ref "MCU1") (pin "39") (pinfunction "PC8_39") (pintype "bidirectional"))
    )
    (net (code "116") (name "unconnected-(MCU1-PC9-Pad40)") (class "Default")
      (node (ref "MCU1") (pin "40") (pinfunction "PC9_40") (pintype "bidirectional"))
    )
    (net (code "117") (name "unconnected-(MCU1-PC12-Pad53)") (class "Default")
      (node (ref "MCU1") (pin "53") (pinfunction "PC12_53") (pintype "bidirectional"))
    )
    (net (code "118") (name "unconnected-(MCU1-PC13-Pad2)") (class "Default")
      (node (ref "MCU1") (pin "2") (pinfunction "PC13_2") (pintype "bidirectional"))
    )
    (net (code "119") (name "unconnected-(MCU1-PC14-Pad3)") (class "Default")
      (node (ref "MCU1") (pin "3") (pinfunction "PC14_3") (pintype "bidirectional"))
    )
    (net (code "120") (name "unconnected-(MCU1-PC15-Pad4)") (class "Default")
      (node (ref "MCU1") (pin "4") (pinfunction "PC15_4") (pintype "bidirectional"))
    )
    (net (code "121") (name "unconnected-(MCU1-PD2-Pad54)") (class "Default")
      (node (ref "MCU1") (pin "54") (pinfunction "PD2_54") (pintype "bidirectional"))
    )
    (net (code "122") (name "unconnected-(MCU1-VBAT-Pad1)") (class "Default")
      (node (ref "MCU1") (pin "1") (pinfunction "VBAT_1") (pintype "bidirectional"))
    )
  )
)
